# 74273_output_port.net
KiCad netlist of a schematic drawn in EAGLE
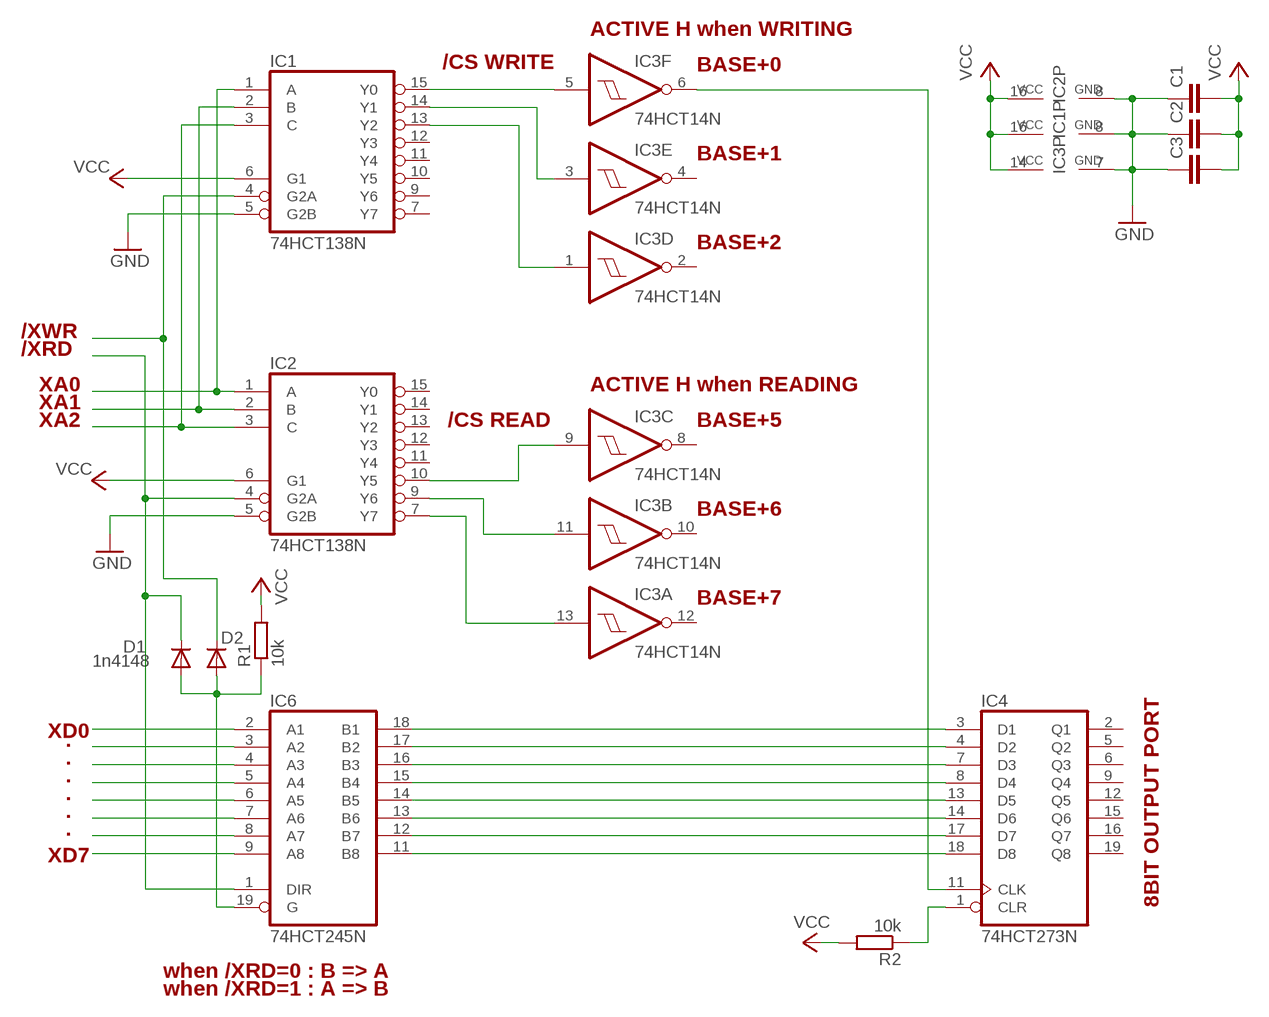
[diagram p0: schematic, sheet 1]

(export (version "E")
  (design (tool "Eeschema 10.0.6"))
  (components
    (comp (ref "C1")
      (value "C-EU025-024X044")
      (footprint "eagle-import:C025-024X044")
      (libsource (lib "eagle-import") (part "C-EU025-024X044"))
    )
    (comp (ref "C2")
      (value "C-EU025-024X044")
      (footprint "eagle-import:C025-024X044")
      (libsource (lib "eagle-import") (part "C-EU025-024X044"))
    )
    (comp (ref "C3")
      (value "C-EU025-024X044")
      (footprint "eagle-import:C025-024X044")
      (libsource (lib "eagle-import") (part "C-EU025-024X044"))
    )
    (comp (ref "D1")
      (value "1n4148")
      (footprint "eagle-import:SMA-DO214AC")
      (libsource (lib "eagle-import") (part "GF1"))
    )
    (comp (ref "D2")
      (value "GF1")
      (footprint "eagle-import:SMA-DO214AC")
      (libsource (lib "eagle-import") (part "GF1"))
    )
    (comp (ref "IC1")
      (value "74HCT138N")
      (footprint "eagle-import:DIL16")
      (libsource (lib "eagle-import") (part "74138NHCT"))
    )
    (comp (ref "IC2")
      (value "74HCT138N")
      (footprint "eagle-import:DIL16")
      (libsource (lib "eagle-import") (part "74138NHCT"))
    )
    (comp (ref "IC3")
      (value "74HCT14N")
      (footprint "eagle-import:DIL14")
      (libsource (lib "eagle-import") (part "7414NHCT"))
    )
    (comp (ref "IC4")
      (value "74HCT273N")
      (footprint "eagle-import:DIL20")
      (libsource (lib "eagle-import") (part "74273NHCT"))
    )
    (comp (ref "IC6")
      (value "74HCT245N")
      (footprint "eagle-import:DIL20")
      (libsource (lib "eagle-import") (part "74245NLS"))
    )
    (comp (ref "R1")
      (value "10k")
      (footprint "eagle-import:0204_5")
      (libsource (lib "eagle-import") (part "R-EU_0204/5"))
    )
    (comp (ref "R2")
      (value "10k")
      (footprint "eagle-import:0204_5")
      (libsource (lib "eagle-import") (part "R-EU_0204/5"))
    )
  )
  (nets
    (net (code "1") (name "GND") (class "Default")
      (node (ref "C1") (pin "1") (pinfunction "1_1") (pintype "passive"))
      (node (ref "C2") (pin "1") (pinfunction "1_1") (pintype "passive"))
      (node (ref "C3") (pin "1") (pinfunction "1_1") (pintype "passive"))
      (node (ref "IC1") (pin "5") (pinfunction "G2B_5") (pintype "input"))
      (node (ref "IC1") (pin "8") (pinfunction "GND_8") (pintype "power_in"))
      (node (ref "IC2") (pin "5") (pinfunction "G2B_5") (pintype "input"))
      (node (ref "IC2") (pin "8") (pinfunction "GND_8") (pintype "power_in"))
      (node (ref "IC3") (pin "7") (pinfunction "GND_7") (pintype "power_in"))
    )
    (net (code "2") (name "Net-(D1-C)") (class "Default")
      (node (ref "D1") (pin "K") (pinfunction "C_K") (pintype "passive"))
      (node (ref "IC2") (pin "4") (pinfunction "G2A_4") (pintype "input"))
      (node (ref "IC6") (pin "1") (pinfunction "DIR_1") (pintype "input"))
    )
    (net (code "3") (name "Net-(D2-C)") (class "Default")
      (node (ref "D2") (pin "K") (pinfunction "C_K") (pintype "passive"))
      (node (ref "IC1") (pin "4") (pinfunction "G2A_4") (pintype "input"))
    )
    (net (code "4") (name "Net-(IC1A-A)") (class "Default")
      (node (ref "IC1") (pin "1") (pinfunction "A_1") (pintype "input"))
      (node (ref "IC2") (pin "1") (pinfunction "A_1") (pintype "input"))
    )
    (net (code "5") (name "Net-(IC1A-B)") (class "Default")
      (node (ref "IC1") (pin "2") (pinfunction "B_2") (pintype "input"))
      (node (ref "IC2") (pin "2") (pinfunction "B_2") (pintype "input"))
    )
    (net (code "6") (name "Net-(IC1A-C)") (class "Default")
      (node (ref "IC1") (pin "3") (pinfunction "C_3") (pintype "input"))
      (node (ref "IC2") (pin "3") (pinfunction "C_3") (pintype "input"))
    )
    (net (code "7") (name "Net-(IC1A-Y0)") (class "Default")
      (node (ref "IC1") (pin "15") (pinfunction "Y0_15") (pintype "output"))
      (node (ref "IC3") (pin "5") (pinfunction "I_5") (pintype "input"))
    )
    (net (code "8") (name "Net-(IC1A-Y1)") (class "Default")
      (node (ref "IC1") (pin "14") (pinfunction "Y1_14") (pintype "output"))
      (node (ref "IC3") (pin "3") (pinfunction "I_3") (pintype "input"))
    )
    (net (code "9") (name "Net-(IC1A-Y2)") (class "Default")
      (node (ref "IC1") (pin "13") (pinfunction "Y2_13") (pintype "output"))
      (node (ref "IC3") (pin "1") (pinfunction "I_1") (pintype "input"))
    )
    (net (code "10") (name "Net-(IC2A-Y5)") (class "Default")
      (node (ref "IC2") (pin "10") (pinfunction "Y5_10") (pintype "output"))
      (node (ref "IC3") (pin "9") (pinfunction "I_9") (pintype "input"))
    )
    (net (code "11") (name "Net-(IC2A-Y6)") (class "Default")
      (node (ref "IC2") (pin "9") (pinfunction "Y6_9") (pintype "output"))
      (node (ref "IC3") (pin "11") (pinfunction "I_11") (pintype "input"))
    )
    (net (code "12") (name "Net-(IC2A-Y7)") (class "Default")
      (node (ref "IC2") (pin "7") (pinfunction "Y7_7") (pintype "output"))
      (node (ref "IC3") (pin "13") (pinfunction "I_13") (pintype "input"))
    )
    (net (code "13") (name "Net-(IC3F-O)") (class "Default")
      (node (ref "IC3") (pin "6") (pinfunction "O_6") (pintype "output"))
      (node (ref "IC4") (pin "11") (pinfunction "CLK_11") (pintype "input"))
    )
    (net (code "14") (name "Net-(IC4A-CLR)") (class "Default")
      (node (ref "IC4") (pin "1") (pinfunction "CLR_1") (pintype "input"))
      (node (ref "R2") (pin "1") (pinfunction "1_1") (pintype "passive"))
    )
    (net (code "15") (name "Net-(IC4A-D1)") (class "Default")
      (node (ref "IC4") (pin "3") (pinfunction "D1_3") (pintype "input"))
      (node (ref "IC6") (pin "18") (pinfunction "B1_18") (pintype "bidirectional"))
    )
    (net (code "16") (name "Net-(IC4A-D2)") (class "Default")
      (node (ref "IC4") (pin "4") (pinfunction "D2_4") (pintype "input"))
      (node (ref "IC6") (pin "17") (pinfunction "B2_17") (pintype "bidirectional"))
    )
    (net (code "17") (name "Net-(IC4A-D3)") (class "Default")
      (node (ref "IC4") (pin "7") (pinfunction "D3_7") (pintype "input"))
      (node (ref "IC6") (pin "16") (pinfunction "B3_16") (pintype "bidirectional"))
    )
    (net (code "18") (name "Net-(IC4A-D4)") (class "Default")
      (node (ref "IC4") (pin "8") (pinfunction "D4_8") (pintype "input"))
      (node (ref "IC6") (pin "15") (pinfunction "B4_15") (pintype "bidirectional"))
    )
    (net (code "19") (name "Net-(IC4A-D5)") (class "Default")
      (node (ref "IC4") (pin "13") (pinfunction "D5_13") (pintype "input"))
      (node (ref "IC6") (pin "14") (pinfunction "B5_14") (pintype "bidirectional"))
    )
    (net (code "20") (name "Net-(IC4A-D6)") (class "Default")
      (node (ref "IC4") (pin "14") (pinfunction "D6_14") (pintype "input"))
      (node (ref "IC6") (pin "13") (pinfunction "B6_13") (pintype "bidirectional"))
    )
    (net (code "21") (name "Net-(IC4A-D7)") (class "Default")
      (node (ref "IC4") (pin "17") (pinfunction "D7_17") (pintype "input"))
      (node (ref "IC6") (pin "12") (pinfunction "B7_12") (pintype "bidirectional"))
    )
    (net (code "22") (name "Net-(IC4A-D8)") (class "Default")
      (node (ref "IC4") (pin "18") (pinfunction "D8_18") (pintype "input"))
      (node (ref "IC6") (pin "11") (pinfunction "B8_11") (pintype "bidirectional"))
    )
    (net (code "23") (name "Net-(IC6A-G)") (class "Default")
      (node (ref "D1") (pin "A") (pinfunction "A_A") (pintype "passive"))
      (node (ref "D2") (pin "A") (pinfunction "A_A") (pintype "passive"))
      (node (ref "IC6") (pin "19") (pinfunction "G_19") (pintype "input"))
      (node (ref "R1") (pin "1") (pinfunction "1_1") (pintype "passive"))
    )
    (net (code "24") (name "VCC") (class "Default")
      (node (ref "C1") (pin "2") (pinfunction "2_2") (pintype "passive"))
      (node (ref "C2") (pin "2") (pinfunction "2_2") (pintype "passive"))
      (node (ref "C3") (pin "2") (pinfunction "2_2") (pintype "passive"))
      (node (ref "IC1") (pin "16") (pinfunction "VCC_16") (pintype "power_in"))
      (node (ref "IC1") (pin "6") (pinfunction "G1_6") (pintype "input"))
      (node (ref "IC2") (pin "16") (pinfunction "VCC_16") (pintype "power_in"))
      (node (ref "IC2") (pin "6") (pinfunction "G1_6") (pintype "input"))
      (node (ref "IC3") (pin "14") (pinfunction "VCC_14") (pintype "power_in"))
      (node (ref "R1") (pin "2") (pinfunction "2_2") (pintype "passive"))
      (node (ref "R2") (pin "2") (pinfunction "2_2") (pintype "passive"))
    )
    (net (code "25") (name "unconnected-(IC1A-Y3-Pad12)") (class "Default")
      (node (ref "IC1") (pin "12") (pinfunction "Y3_12") (pintype "output"))
    )
    (net (code "26") (name "unconnected-(IC1A-Y4-Pad11)") (class "Default")
      (node (ref "IC1") (pin "11") (pinfunction "Y4_11") (pintype "output"))
    )
    (net (code "27") (name "unconnected-(IC1A-Y5-Pad10)") (class "Default")
      (node (ref "IC1") (pin "10") (pinfunction "Y5_10") (pintype "output"))
    )
    (net (code "28") (name "unconnected-(IC1A-Y6-Pad9)") (class "Default")
      (node (ref "IC1") (pin "9") (pinfunction "Y6_9") (pintype "output"))
    )
    (net (code "29") (name "unconnected-(IC1A-Y7-Pad7)") (class "Default")
      (node (ref "IC1") (pin "7") (pinfunction "Y7_7") (pintype "output"))
    )
    (net (code "30") (name "unconnected-(IC2A-Y0-Pad15)") (class "Default")
      (node (ref "IC2") (pin "15") (pinfunction "Y0_15") (pintype "output"))
    )
    (net (code "31") (name "unconnected-(IC2A-Y1-Pad14)") (class "Default")
      (node (ref "IC2") (pin "14") (pinfunction "Y1_14") (pintype "output"))
    )
    (net (code "32") (name "unconnected-(IC2A-Y2-Pad13)") (class "Default")
      (node (ref "IC2") (pin "13") (pinfunction "Y2_13") (pintype "output"))
    )
    (net (code "33") (name "unconnected-(IC2A-Y3-Pad12)") (class "Default")
      (node (ref "IC2") (pin "12") (pinfunction "Y3_12") (pintype "output"))
    )
    (net (code "34") (name "unconnected-(IC2A-Y4-Pad11)") (class "Default")
      (node (ref "IC2") (pin "11") (pinfunction "Y4_11") (pintype "output"))
    )
    (net (code "35") (name "unconnected-(IC3A-O-Pad12)") (class "Default")
      (node (ref "IC3") (pin "12") (pinfunction "O_12") (pintype "output"))
    )
    (net (code "36") (name "unconnected-(IC3B-O-Pad10)") (class "Default")
      (node (ref "IC3") (pin "10") (pinfunction "O_10") (pintype "output"))
    )
    (net (code "37") (name "unconnected-(IC3C-O-Pad8)") (class "Default")
      (node (ref "IC3") (pin "8") (pinfunction "O_8") (pintype "output"))
    )
    (net (code "38") (name "unconnected-(IC3D-O-Pad2)") (class "Default")
      (node (ref "IC3") (pin "2") (pinfunction "O_2") (pintype "output"))
    )
    (net (code "39") (name "unconnected-(IC3E-O-Pad4)") (class "Default")
      (node (ref "IC3") (pin "4") (pinfunction "O_4") (pintype "output"))
    )
    (net (code "40") (name "unconnected-(IC4A-Q1-Pad2)") (class "Default")
      (node (ref "IC4") (pin "2") (pinfunction "Q1_2") (pintype "output"))
    )
    (net (code "41") (name "unconnected-(IC4A-Q2-Pad5)") (class "Default")
      (node (ref "IC4") (pin "5") (pinfunction "Q2_5") (pintype "output"))
    )
    (net (code "42") (name "unconnected-(IC4A-Q3-Pad6)") (class "Default")
      (node (ref "IC4") (pin "6") (pinfunction "Q3_6") (pintype "output"))
    )
    (net (code "43") (name "unconnected-(IC4A-Q4-Pad9)") (class "Default")
      (node (ref "IC4") (pin "9") (pinfunction "Q4_9") (pintype "output"))
    )
    (net (code "44") (name "unconnected-(IC4A-Q5-Pad12)") (class "Default")
      (node (ref "IC4") (pin "12") (pinfunction "Q5_12") (pintype "output"))
    )
    (net (code "45") (name "unconnected-(IC4A-Q6-Pad15)") (class "Default")
      (node (ref "IC4") (pin "15") (pinfunction "Q6_15") (pintype "output"))
    )
    (net (code "46") (name "unconnected-(IC4A-Q7-Pad16)") (class "Default")
      (node (ref "IC4") (pin "16") (pinfunction "Q7_16") (pintype "output"))
    )
    (net (code "47") (name "unconnected-(IC4A-Q8-Pad19)") (class "Default")
      (node (ref "IC4") (pin "19") (pinfunction "Q8_19") (pintype "output"))
    )
    (net (code "48") (name "unconnected-(IC6A-A1-Pad2)") (class "Default")
      (node (ref "IC6") (pin "2") (pinfunction "A1_2") (pintype "bidirectional"))
    )
    (net (code "49") (name "unconnected-(IC6A-A2-Pad3)") (class "Default")
      (node (ref "IC6") (pin "3") (pinfunction "A2_3") (pintype "bidirectional"))
    )
    (net (code "50") (name "unconnected-(IC6A-A3-Pad4)") (class "Default")
      (node (ref "IC6") (pin "4") (pinfunction "A3_4") (pintype "bidirectional"))
    )
    (net (code "51") (name "unconnected-(IC6A-A4-Pad5)") (class "Default")
      (node (ref "IC6") (pin "5") (pinfunction "A4_5") (pintype "bidirectional"))
    )
    (net (code "52") (name "unconnected-(IC6A-A5-Pad6)") (class "Default")
      (node (ref "IC6") (pin "6") (pinfunction "A5_6") (pintype "bidirectional"))
    )
    (net (code "53") (name "unconnected-(IC6A-A6-Pad7)") (class "Default")
      (node (ref "IC6") (pin "7") (pinfunction "A6_7") (pintype "bidirectional"))
    )
    (net (code "54") (name "unconnected-(IC6A-A7-Pad8)") (class "Default")
      (node (ref "IC6") (pin "8") (pinfunction "A7_8") (pintype "bidirectional"))
    )
    (net (code "55") (name "unconnected-(IC6A-A8-Pad9)") (class "Default")
      (node (ref "IC6") (pin "9") (pinfunction "A8_9") (pintype "bidirectional"))
    )
  )
)
